# pxdr-001.net
KiCad netlist of a schematic drawn in EAGLE
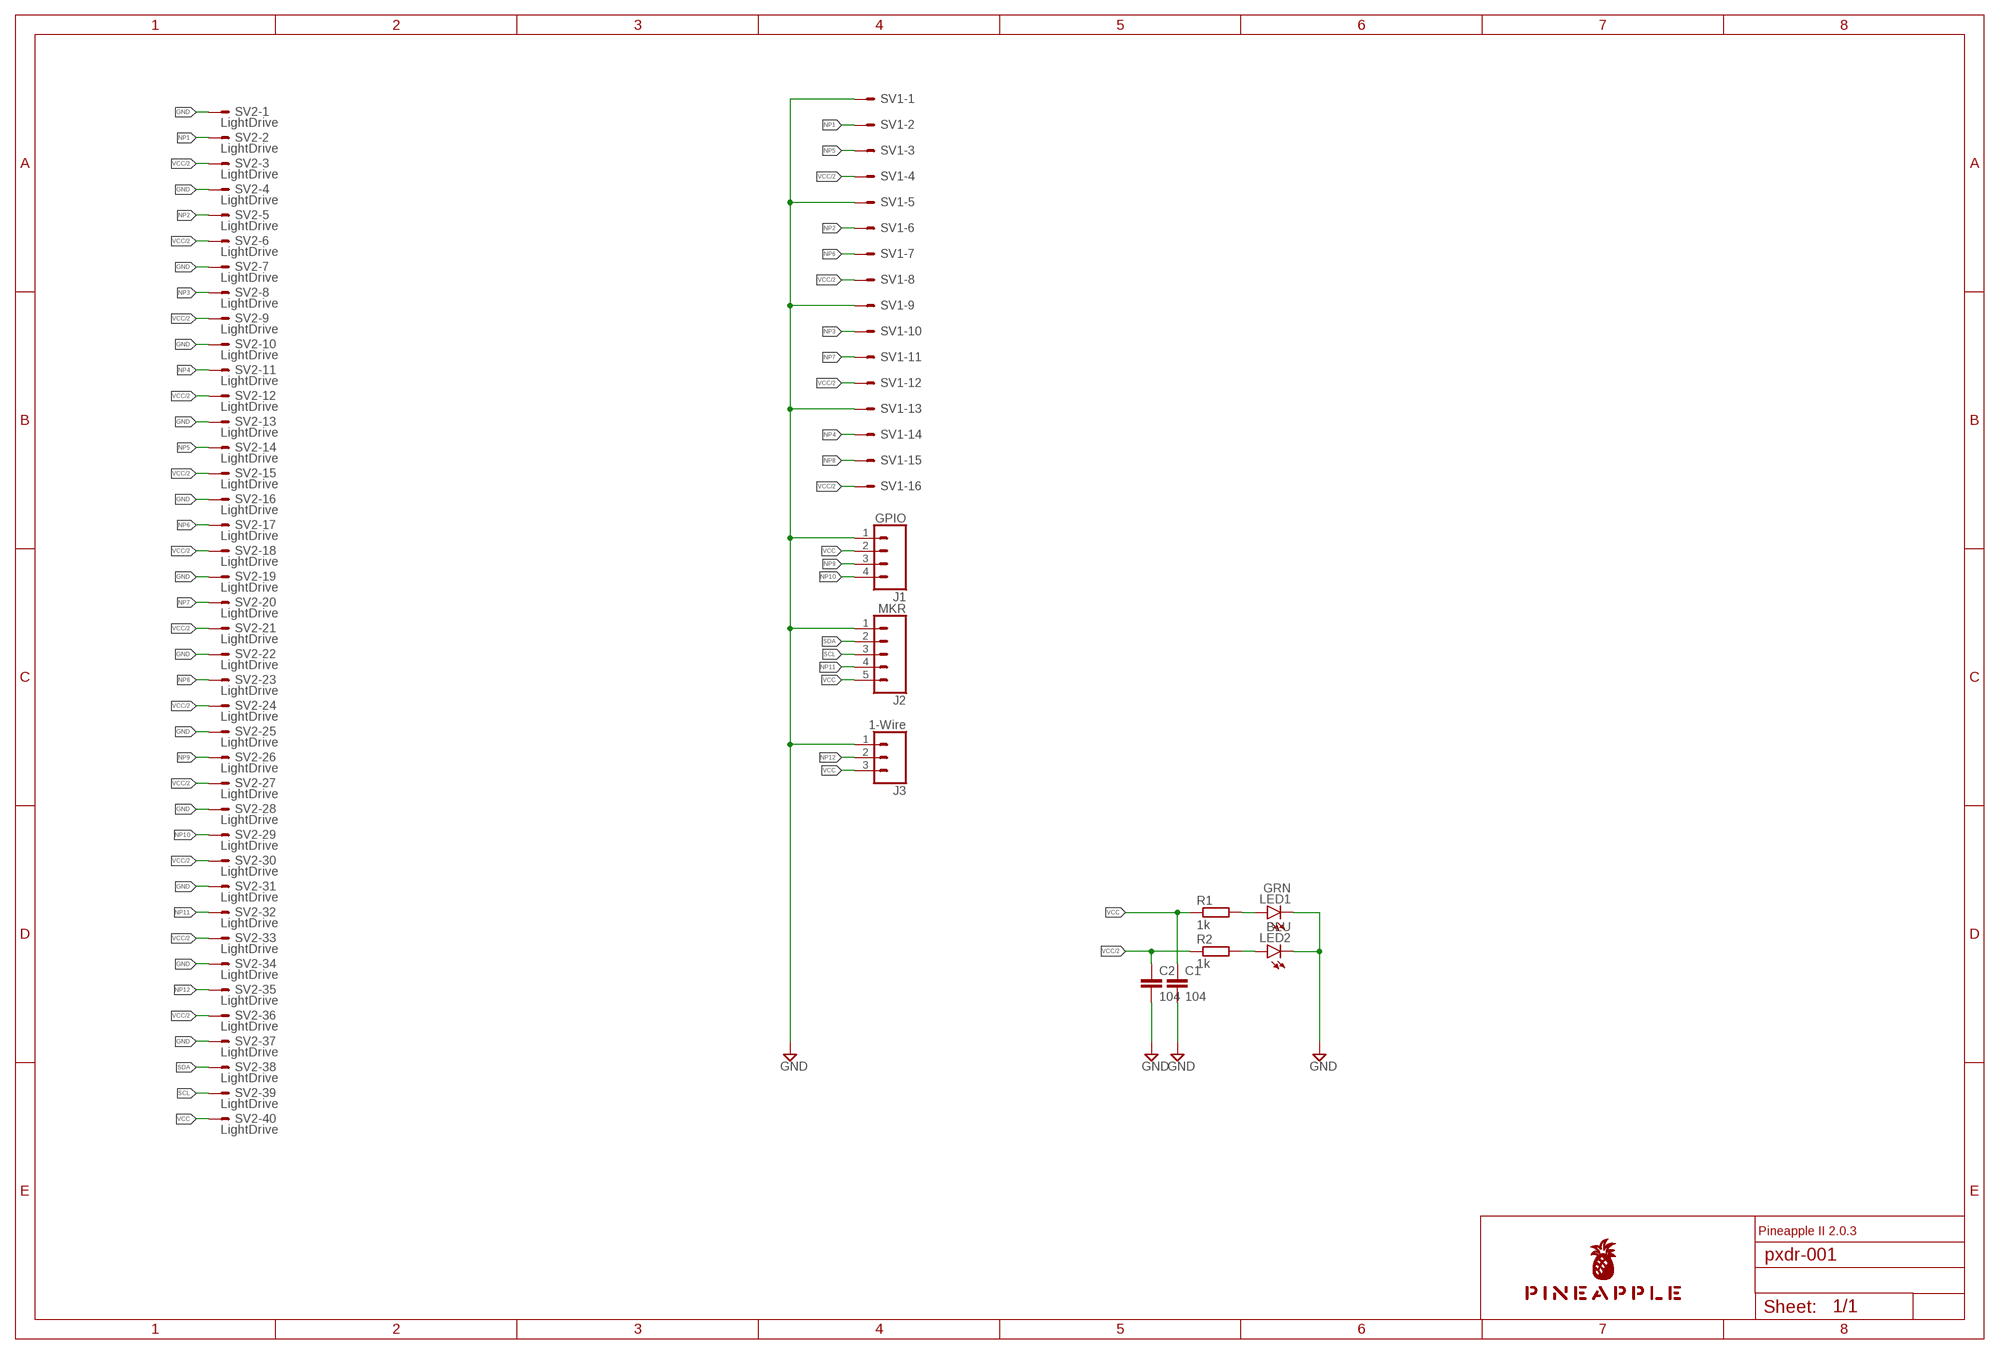
[diagram p0: schematic, sheet 1]

(export (version "E")
  (design (tool "Eeschema 10.0.6"))
  (components
    (comp (ref "C1")
      (value "104")
      (footprint "eagle-import:C025-025X050")
      (libsource (lib "eagle-import") (part "C-EU025-025X050"))
    )
    (comp (ref "C2")
      (value "104")
      (footprint "eagle-import:C025-025X050")
      (libsource (lib "eagle-import") (part "C-EU025-025X050"))
    )
    (comp (ref "J1")
      (value "GPIO")
      (footprint "eagle-import:JST-4-PTH")
      (libsource (lib "eagle-import") (part "CONN_04JST-PTH"))
    )
    (comp (ref "J2")
      (value "MKR")
      (footprint "eagle-import:JST-5-PTH")
      (libsource (lib "eagle-import") (part "CONN_05JST"))
    )
    (comp (ref "J3")
      (value "1-Wire")
      (footprint "eagle-import:JST-3-PTH")
      (libsource (lib "eagle-import") (part "CONN_03JST-PTH"))
    )
    (comp (ref "LED1")
      (value "GRN")
      (footprint "eagle-import:Q62902-B152")
      (libsource (lib "eagle-import") (part "LEDB152"))
    )
    (comp (ref "LED2")
      (value "BLU")
      (footprint "eagle-import:Q62902-B152")
      (libsource (lib "eagle-import") (part "LEDB152"))
    )
    (comp (ref "R1")
      (value "1k")
      (footprint "eagle-import:0204_5")
      (libsource (lib "eagle-import") (part "R-EU_0204/5"))
    )
    (comp (ref "R2")
      (value "1k")
      (footprint "eagle-import:0204_5")
      (libsource (lib "eagle-import") (part "R-EU_0204/5"))
    )
    (comp (ref "SV1")
      (value "ML16LE")
      (footprint "eagle-import:ML16L")
      (libsource (lib "eagle-import") (part "ML16LE"))
    )
    (comp (ref "SV2")
      (value "LightDrive")
      (footprint "eagle-import:ML40L")
      (libsource (lib "eagle-import") (part "ML40LE"))
    )
    (comp (ref "U$1")
      (value "PINEAPPLE450_SILK")
      (footprint "eagle-import:PINEAPPLE450_SILK")
      (libsource (lib "eagle-import") (part "PINEAPPLE450_SILK"))
    )
  )
  (nets
    (net (code "1") (name "GND") (class "Default")
      (node (ref "C1") (pin "2") (pinfunction "2_2") (pintype "passive"))
      (node (ref "C2") (pin "2") (pinfunction "2_2") (pintype "passive"))
      (node (ref "J1") (pin "1") (pinfunction "1_1") (pintype "passive"))
      (node (ref "J2") (pin "1") (pinfunction "1_1") (pintype "passive"))
      (node (ref "J3") (pin "1") (pinfunction "1_1") (pintype "passive"))
      (node (ref "LED1") (pin "K") (pinfunction "C_K") (pintype "passive"))
      (node (ref "LED2") (pin "K") (pinfunction "C_K") (pintype "passive"))
      (node (ref "SV1") (pin "1") (pinfunction "S_1") (pintype "passive"))
      (node (ref "SV1") (pin "13") (pinfunction "S_13") (pintype "passive"))
      (node (ref "SV1") (pin "5") (pinfunction "S_5") (pintype "passive"))
      (node (ref "SV1") (pin "9") (pinfunction "S_9") (pintype "passive"))
      (node (ref "SV2") (pin "1") (pinfunction "S_1") (pintype "passive"))
      (node (ref "SV2") (pin "10") (pinfunction "S_10") (pintype "passive"))
      (node (ref "SV2") (pin "13") (pinfunction "S_13") (pintype "passive"))
      (node (ref "SV2") (pin "16") (pinfunction "S_16") (pintype "passive"))
      (node (ref "SV2") (pin "19") (pinfunction "S_19") (pintype "passive"))
      (node (ref "SV2") (pin "22") (pinfunction "S_22") (pintype "passive"))
      (node (ref "SV2") (pin "25") (pinfunction "S_25") (pintype "passive"))
      (node (ref "SV2") (pin "28") (pinfunction "S_28") (pintype "passive"))
      (node (ref "SV2") (pin "31") (pinfunction "S_31") (pintype "passive"))
      (node (ref "SV2") (pin "34") (pinfunction "S_34") (pintype "passive"))
      (node (ref "SV2") (pin "37") (pinfunction "S_37") (pintype "passive"))
      (node (ref "SV2") (pin "4") (pinfunction "S_4") (pintype "passive"))
      (node (ref "SV2") (pin "7") (pinfunction "S_7") (pintype "passive"))
    )
    (net (code "2") (name "NP1") (class "Default")
      (node (ref "SV1") (pin "2") (pinfunction "S_2") (pintype "passive"))
      (node (ref "SV2") (pin "2") (pinfunction "S_2") (pintype "passive"))
    )
    (net (code "3") (name "NP2") (class "Default")
      (node (ref "SV1") (pin "6") (pinfunction "S_6") (pintype "passive"))
      (node (ref "SV2") (pin "5") (pinfunction "S_5") (pintype "passive"))
    )
    (net (code "4") (name "NP3") (class "Default")
      (node (ref "SV1") (pin "10") (pinfunction "S_10") (pintype "passive"))
      (node (ref "SV2") (pin "8") (pinfunction "S_8") (pintype "passive"))
    )
    (net (code "5") (name "NP4") (class "Default")
      (node (ref "SV1") (pin "14") (pinfunction "S_14") (pintype "passive"))
      (node (ref "SV2") (pin "11") (pinfunction "S_11") (pintype "passive"))
    )
    (net (code "6") (name "NP5") (class "Default")
      (node (ref "SV1") (pin "3") (pinfunction "S_3") (pintype "passive"))
      (node (ref "SV2") (pin "14") (pinfunction "S_14") (pintype "passive"))
    )
    (net (code "7") (name "NP6") (class "Default")
      (node (ref "SV1") (pin "7") (pinfunction "S_7") (pintype "passive"))
      (node (ref "SV2") (pin "17") (pinfunction "S_17") (pintype "passive"))
    )
    (net (code "8") (name "NP7") (class "Default")
      (node (ref "SV1") (pin "11") (pinfunction "S_11") (pintype "passive"))
      (node (ref "SV2") (pin "20") (pinfunction "S_20") (pintype "passive"))
    )
    (net (code "9") (name "NP8") (class "Default")
      (node (ref "SV1") (pin "15") (pinfunction "S_15") (pintype "passive"))
      (node (ref "SV2") (pin "23") (pinfunction "S_23") (pintype "passive"))
    )
    (net (code "10") (name "NP9") (class "Default")
      (node (ref "J1") (pin "3") (pinfunction "3_3") (pintype "passive"))
      (node (ref "SV2") (pin "26") (pinfunction "S_26") (pintype "passive"))
    )
    (net (code "11") (name "NP10") (class "Default")
      (node (ref "J1") (pin "4") (pinfunction "4_4") (pintype "passive"))
      (node (ref "SV2") (pin "29") (pinfunction "S_29") (pintype "passive"))
    )
    (net (code "12") (name "NP11") (class "Default")
      (node (ref "J2") (pin "4") (pinfunction "4_4") (pintype "passive"))
      (node (ref "SV2") (pin "32") (pinfunction "S_32") (pintype "passive"))
    )
    (net (code "13") (name "NP12") (class "Default")
      (node (ref "J3") (pin "2") (pinfunction "2_2") (pintype "passive"))
      (node (ref "SV2") (pin "35") (pinfunction "S_35") (pintype "passive"))
    )
    (net (code "14") (name "Net-(LED1-PadA)") (class "Default")
      (node (ref "LED1") (pin "A") (pinfunction "A_A") (pintype "passive"))
      (node (ref "R1") (pin "2") (pinfunction "2_2") (pintype "passive"))
    )
    (net (code "15") (name "Net-(LED2-PadA)") (class "Default")
      (node (ref "LED2") (pin "A") (pinfunction "A_A") (pintype "passive"))
      (node (ref "R2") (pin "2") (pinfunction "2_2") (pintype "passive"))
    )
    (net (code "16") (name "SCL") (class "Default")
      (node (ref "J2") (pin "3") (pinfunction "3_3") (pintype "passive"))
      (node (ref "SV2") (pin "39") (pinfunction "S_39") (pintype "passive"))
    )
    (net (code "17") (name "SDA") (class "Default")
      (node (ref "J2") (pin "2") (pinfunction "2_2") (pintype "passive"))
      (node (ref "SV2") (pin "38") (pinfunction "S_38") (pintype "passive"))
    )
    (net (code "18") (name "VCC") (class "Default")
      (node (ref "C1") (pin "1") (pinfunction "1_1") (pintype "passive"))
      (node (ref "J1") (pin "2") (pinfunction "2_2") (pintype "passive"))
      (node (ref "J2") (pin "5") (pinfunction "5_5") (pintype "passive"))
      (node (ref "J3") (pin "3") (pinfunction "3_3") (pintype "passive"))
      (node (ref "R1") (pin "1") (pinfunction "1_1") (pintype "passive"))
      (node (ref "SV2") (pin "40") (pinfunction "S_40") (pintype "passive"))
    )
    (net (code "19") (name "VCC{slash}2") (class "Default")
      (node (ref "C2") (pin "1") (pinfunction "1_1") (pintype "passive"))
      (node (ref "R2") (pin "1") (pinfunction "1_1") (pintype "passive"))
      (node (ref "SV1") (pin "12") (pinfunction "S_12") (pintype "passive"))
      (node (ref "SV1") (pin "16") (pinfunction "S_16") (pintype "passive"))
      (node (ref "SV1") (pin "4") (pinfunction "S_4") (pintype "passive"))
      (node (ref "SV1") (pin "8") (pinfunction "S_8") (pintype "passive"))
      (node (ref "SV2") (pin "12") (pinfunction "S_12") (pintype "passive"))
      (node (ref "SV2") (pin "15") (pinfunction "S_15") (pintype "passive"))
      (node (ref "SV2") (pin "18") (pinfunction "S_18") (pintype "passive"))
      (node (ref "SV2") (pin "21") (pinfunction "S_21") (pintype "passive"))
      (node (ref "SV2") (pin "24") (pinfunction "S_24") (pintype "passive"))
      (node (ref "SV2") (pin "27") (pinfunction "S_27") (pintype "passive"))
      (node (ref "SV2") (pin "3") (pinfunction "S_3") (pintype "passive"))
      (node (ref "SV2") (pin "30") (pinfunction "S_30") (pintype "passive"))
      (node (ref "SV2") (pin "33") (pinfunction "S_33") (pintype "passive"))
      (node (ref "SV2") (pin "36") (pinfunction "S_36") (pintype "passive"))
      (node (ref "SV2") (pin "6") (pinfunction "S_6") (pintype "passive"))
      (node (ref "SV2") (pin "9") (pinfunction "S_9") (pintype "passive"))
    )
  )
)
